# cc1200layout.net
KiCad netlist of a schematic drawn in EAGLE
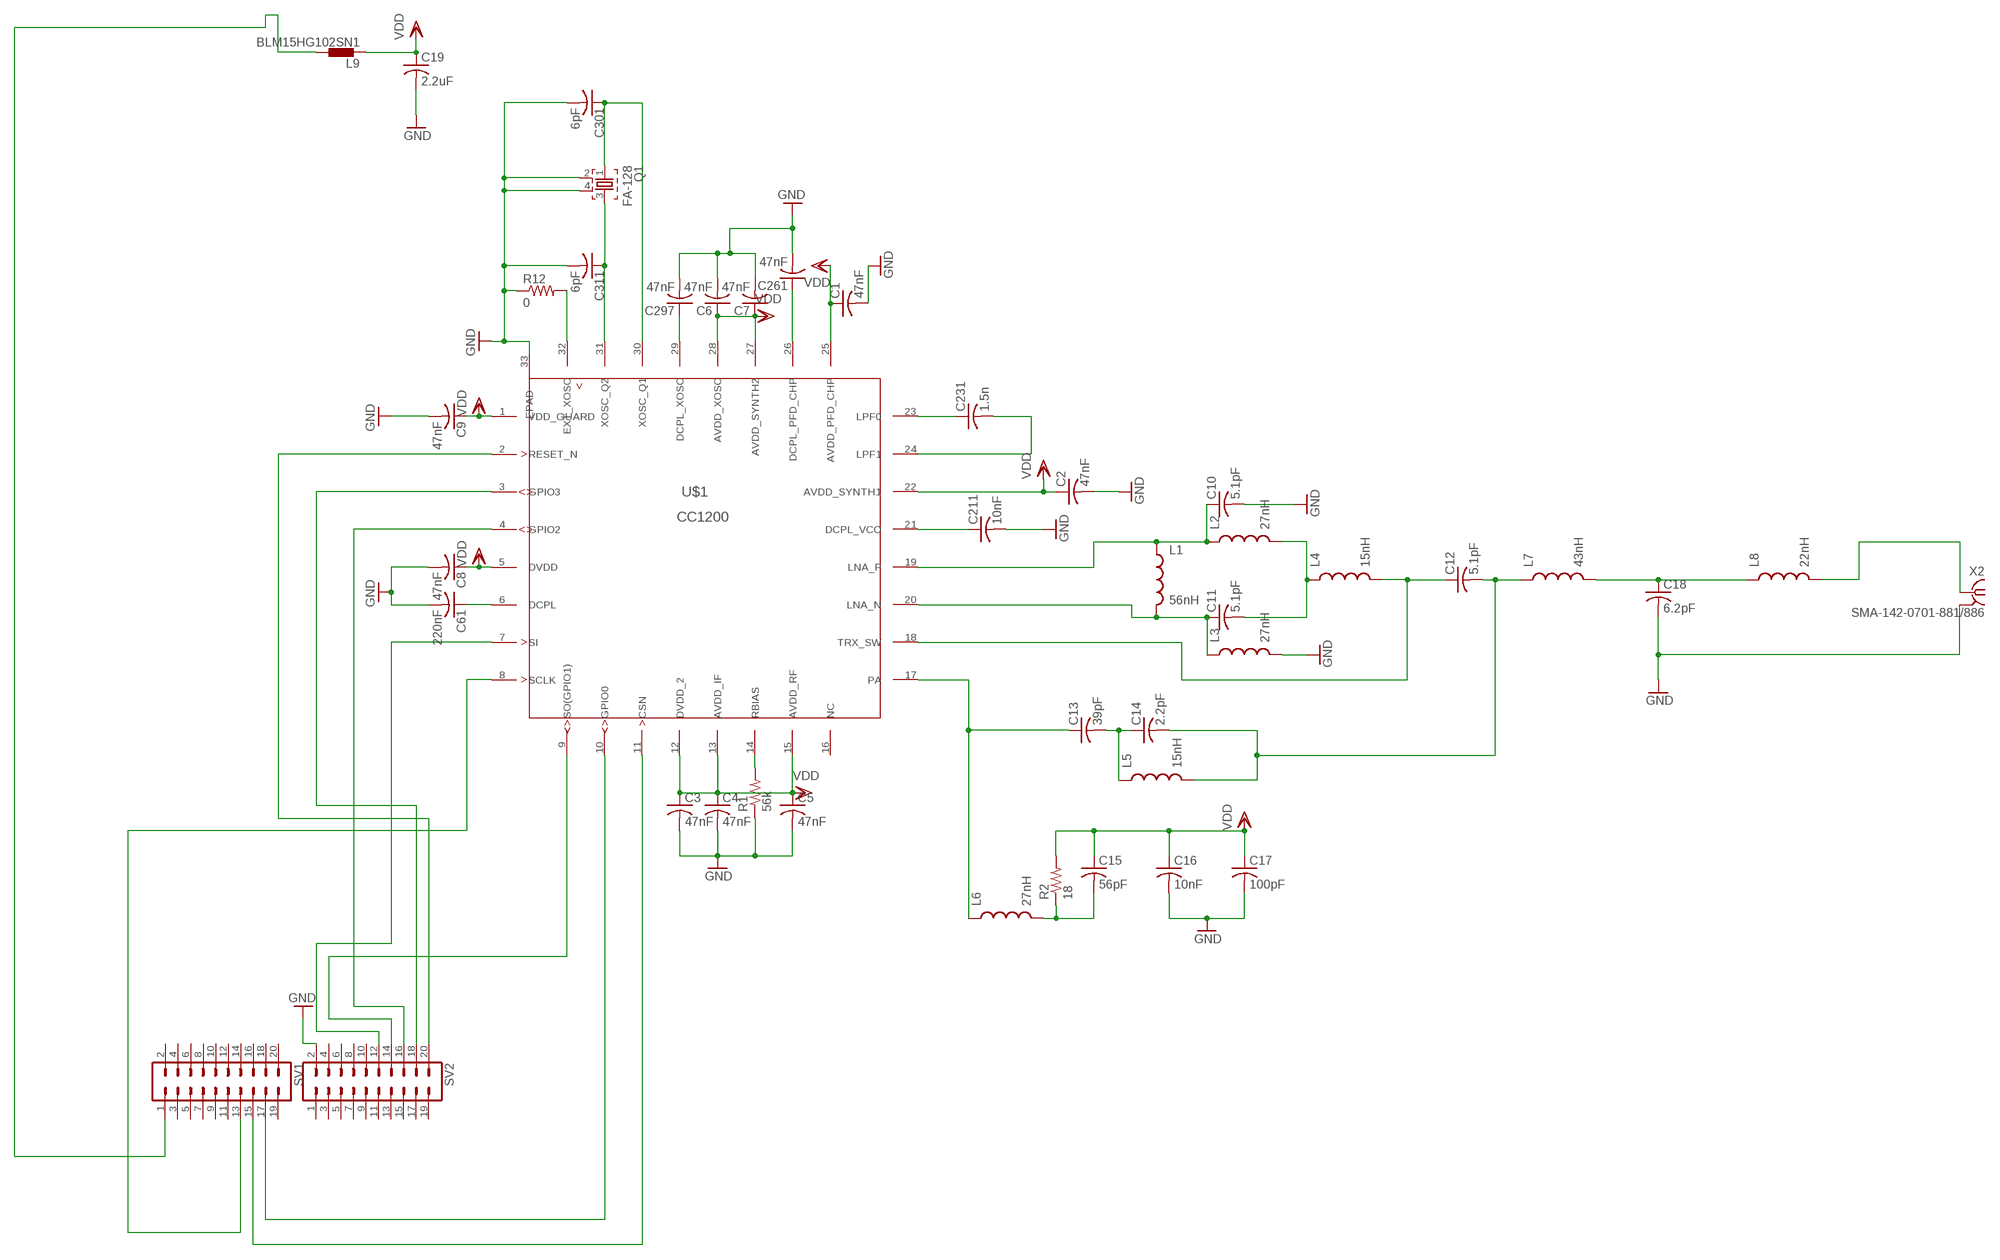
[diagram p0: schematic, sheet 1]

(export (version "E")
  (design (tool "Eeschema 10.0.6"))
  (components
    (comp (ref "C1")
      (value "47nF")
      (footprint "eagle-import:C0402K")
      (libsource (lib "eagle-import") (part "C-USC0402K"))
    )
    (comp (ref "C2")
      (value "47nF")
      (footprint "eagle-import:C0402K")
      (libsource (lib "eagle-import") (part "C-USC0402K"))
    )
    (comp (ref "C3")
      (value "47nF")
      (footprint "eagle-import:C0402K")
      (libsource (lib "eagle-import") (part "C-USC0402K"))
    )
    (comp (ref "C4")
      (value "47nF")
      (footprint "eagle-import:C0402K")
      (libsource (lib "eagle-import") (part "C-USC0402K"))
    )
    (comp (ref "C5")
      (value "47nF")
      (footprint "eagle-import:C0402K")
      (libsource (lib "eagle-import") (part "C-USC0402K"))
    )
    (comp (ref "C6")
      (value "47nF")
      (footprint "eagle-import:C0402K")
      (libsource (lib "eagle-import") (part "C-USC0402K"))
    )
    (comp (ref "C7")
      (value "47nF")
      (footprint "eagle-import:C0402K")
      (libsource (lib "eagle-import") (part "C-USC0402K"))
    )
    (comp (ref "C8")
      (value "47nF")
      (footprint "eagle-import:C0402K")
      (libsource (lib "eagle-import") (part "C-USC0402K"))
    )
    (comp (ref "C9")
      (value "47nF")
      (footprint "eagle-import:C0402K")
      (libsource (lib "eagle-import") (part "C-USC0402K"))
    )
    (comp (ref "C10")
      (value "5.1pF")
      (footprint "eagle-import:C0402K")
      (libsource (lib "eagle-import") (part "C-USC0402K"))
    )
    (comp (ref "C11")
      (value "5.1pF")
      (footprint "eagle-import:C0402K")
      (libsource (lib "eagle-import") (part "C-USC0402K"))
    )
    (comp (ref "C12")
      (value "5.1pF")
      (footprint "eagle-import:C0402K")
      (libsource (lib "eagle-import") (part "C-USC0402K"))
    )
    (comp (ref "C13")
      (value "39pF")
      (footprint "eagle-import:C0402K")
      (libsource (lib "eagle-import") (part "C-USC0402K"))
    )
    (comp (ref "C14")
      (value "2.2pF")
      (footprint "eagle-import:C0402K")
      (libsource (lib "eagle-import") (part "C-USC0402K"))
    )
    (comp (ref "C15")
      (value "56pF")
      (footprint "eagle-import:C0402K")
      (libsource (lib "eagle-import") (part "C-USC0402K"))
    )
    (comp (ref "C16")
      (value "10nF")
      (footprint "eagle-import:C0402K")
      (libsource (lib "eagle-import") (part "C-USC0402K"))
    )
    (comp (ref "C17")
      (value "100pF")
      (footprint "eagle-import:C0402K")
      (libsource (lib "eagle-import") (part "C-USC0402K"))
    )
    (comp (ref "C18")
      (value "6.2pF")
      (footprint "eagle-import:C0402K")
      (libsource (lib "eagle-import") (part "C-USC0402K"))
    )
    (comp (ref "C19")
      (value "2.2uF")
      (footprint "eagle-import:C0603K")
      (libsource (lib "eagle-import") (part "C-USC0603K"))
    )
    (comp (ref "C61")
      (value "220nF")
      (footprint "eagle-import:C0402K")
      (libsource (lib "eagle-import") (part "C-USC0402K"))
    )
    (comp (ref "C211")
      (value "10nF")
      (footprint "eagle-import:C0402K")
      (libsource (lib "eagle-import") (part "C-USC0402K"))
    )
    (comp (ref "C231")
      (value "1.5n")
      (footprint "eagle-import:C0402K")
      (libsource (lib "eagle-import") (part "C-USC0402K"))
    )
    (comp (ref "C261")
      (value "47nF")
      (footprint "eagle-import:C0402K")
      (libsource (lib "eagle-import") (part "C-USC0402K"))
    )
    (comp (ref "C297")
      (value "47nF")
      (footprint "eagle-import:C0402K")
      (libsource (lib "eagle-import") (part "C-USC0402K"))
    )
    (comp (ref "C301")
      (value "6pF")
      (footprint "eagle-import:C0402K")
      (libsource (lib "eagle-import") (part "C-USC0402K"))
    )
    (comp (ref "C311")
      (value "6pF")
      (footprint "eagle-import:C0402K")
      (libsource (lib "eagle-import") (part "C-USC0402K"))
    )
    (comp (ref "L1")
      (value "56nH")
      (footprint "eagle-import:C0402")
      (libsource (lib "eagle-import") (part "INDUCTOR0402"))
    )
    (comp (ref "L2")
      (value "27nH")
      (footprint "eagle-import:C0402")
      (libsource (lib "eagle-import") (part "INDUCTOR0402"))
    )
    (comp (ref "L3")
      (value "27nH")
      (footprint "eagle-import:C0402")
      (libsource (lib "eagle-import") (part "INDUCTOR0402"))
    )
    (comp (ref "L4")
      (value "15nH")
      (footprint "eagle-import:C0402")
      (libsource (lib "eagle-import") (part "INDUCTOR0402"))
    )
    (comp (ref "L5")
      (value "15nH")
      (footprint "eagle-import:C0402")
      (libsource (lib "eagle-import") (part "INDUCTOR0402"))
    )
    (comp (ref "L6")
      (value "27nH")
      (footprint "eagle-import:C0402")
      (libsource (lib "eagle-import") (part "INDUCTOR0402"))
    )
    (comp (ref "L7")
      (value "43nH")
      (footprint "eagle-import:C0402")
      (libsource (lib "eagle-import") (part "INDUCTOR0402"))
    )
    (comp (ref "L8")
      (value "22nH")
      (footprint "eagle-import:C0402")
      (libsource (lib "eagle-import") (part "INDUCTOR0402"))
    )
    (comp (ref "L9")
      (value "BLM15HG102SN1")
      (footprint "eagle-import:0402")
      (libsource (lib "eagle-import") (part "BLM15HG102SN1"))
    )
    (comp (ref "Q1")
      (value "FA-128")
      (footprint "eagle-import:FA-128")
      (libsource (lib "eagle-import") (part "FA-128"))
    )
    (comp (ref "R1")
      (value "56k")
      (footprint "eagle-import:R0402")
      (libsource (lib "eagle-import") (part "R-US_R0402"))
    )
    (comp (ref "R2")
      (value "18")
      (footprint "eagle-import:R0402")
      (libsource (lib "eagle-import") (part "R-US_R0402"))
    )
    (comp (ref "R12")
      (value "0")
      (footprint "eagle-import:R0402")
      (libsource (lib "eagle-import") (part "R-US_R0402"))
    )
    (comp (ref "SV1")
      (value "MA10-2")
      (footprint "eagle-import:MA10-2")
      (libsource (lib "eagle-import") (part "MA10-2"))
    )
    (comp (ref "SV2")
      (value "MA10-2")
      (footprint "eagle-import:MA10-2")
      (libsource (lib "eagle-import") (part "MA10-2"))
    )
    (comp (ref "U$1")
      (value "CC1200")
      (footprint "eagle-import:RHB32_3P45X3P45")
      (libsource (lib "eagle-import") (part "CC1200"))
    )
    (comp (ref "X2")
      (value "SMA-142-0701-881/886")
      (footprint "eagle-import:J502-ND-142-0701-881_886")
      (fields (field (name "MF") "JOHNSON COMPONENTS") (field (name "MPN") "142-0701-881"))
      (libsource (lib "eagle-import") (part "SMA-142-0701-881/886"))
    )
  )
  (nets
    (net (code "1") (name "GND") (class "Default")
      (node (ref "C1") (pin "2") (pinfunction "2_2") (pintype "passive"))
      (node (ref "C10") (pin "2") (pinfunction "2_2") (pintype "passive"))
      (node (ref "C16") (pin "2") (pinfunction "2_2") (pintype "passive"))
      (node (ref "C17") (pin "2") (pinfunction "2_2") (pintype "passive"))
      (node (ref "C18") (pin "2") (pinfunction "2_2") (pintype "passive"))
      (node (ref "C19") (pin "2") (pinfunction "2_2") (pintype "passive"))
      (node (ref "C2") (pin "2") (pinfunction "2_2") (pintype "passive"))
      (node (ref "C211") (pin "2") (pinfunction "2_2") (pintype "passive"))
      (node (ref "C261") (pin "2") (pinfunction "2_2") (pintype "passive"))
      (node (ref "C297") (pin "2") (pinfunction "2_2") (pintype "passive"))
      (node (ref "C3") (pin "2") (pinfunction "2_2") (pintype "passive"))
      (node (ref "C301") (pin "2") (pinfunction "2_2") (pintype "passive"))
      (node (ref "C311") (pin "2") (pinfunction "2_2") (pintype "passive"))
      (node (ref "C4") (pin "2") (pinfunction "2_2") (pintype "passive"))
      (node (ref "C5") (pin "2") (pinfunction "2_2") (pintype "passive"))
      (node (ref "C6") (pin "2") (pinfunction "2_2") (pintype "passive"))
      (node (ref "C61") (pin "2") (pinfunction "2_2") (pintype "passive"))
      (node (ref "C7") (pin "2") (pinfunction "2_2") (pintype "passive"))
      (node (ref "C8") (pin "2") (pinfunction "2_2") (pintype "passive"))
      (node (ref "C9") (pin "2") (pinfunction "2_2") (pintype "passive"))
      (node (ref "L3") (pin "2") (pinfunction "2_2") (pintype "passive"))
      (node (ref "Q1") (pin "2") (pinfunction "2_2") (pintype "passive"))
      (node (ref "Q1") (pin "4") (pinfunction "4_4") (pintype "passive"))
      (node (ref "R1") (pin "1") (pinfunction "1_1") (pintype "passive"))
      (node (ref "R12") (pin "1") (pinfunction "1_1") (pintype "passive"))
      (node (ref "SV2") (pin "2") (pinfunction "2_2") (pintype "passive"))
      (node (ref "U$1") (pin "33") (pinfunction "EPAD_33") (pintype "passive"))
      (node (ref "X2") (pin "G@1") (pinfunction "2_G@1") (pintype "passive"))
      (node (ref "X2") (pin "G@2") (pinfunction "2_G@2") (pintype "passive"))
      (node (ref "X2") (pin "G@3") (pinfunction "2_G@3") (pintype "passive"))
      (node (ref "X2") (pin "G@4") (pinfunction "2_G@4") (pintype "passive"))
    )
    (net (code "2") (name "Net-(C11-Pad2)") (class "Default")
      (node (ref "C11") (pin "2") (pinfunction "2_2") (pintype "passive"))
      (node (ref "L2") (pin "2") (pinfunction "2_2") (pintype "passive"))
      (node (ref "L4") (pin "1") (pinfunction "1_1") (pintype "passive"))
    )
    (net (code "3") (name "Net-(C12-Pad2)") (class "Default")
      (node (ref "C12") (pin "2") (pinfunction "2_2") (pintype "passive"))
      (node (ref "C14") (pin "2") (pinfunction "2_2") (pintype "passive"))
      (node (ref "L5") (pin "2") (pinfunction "2_2") (pintype "passive"))
      (node (ref "L7") (pin "1") (pinfunction "1_1") (pintype "passive"))
    )
    (net (code "4") (name "Net-(C13-Pad2)") (class "Default")
      (node (ref "C13") (pin "2") (pinfunction "2_2") (pintype "passive"))
      (node (ref "C14") (pin "1") (pinfunction "1_1") (pintype "passive"))
      (node (ref "L5") (pin "1") (pinfunction "1_1") (pintype "passive"))
    )
    (net (code "5") (name "Net-(C15-Pad2)") (class "Default")
      (node (ref "C15") (pin "2") (pinfunction "2_2") (pintype "passive"))
      (node (ref "L6") (pin "2") (pinfunction "2_2") (pintype "passive"))
      (node (ref "R2") (pin "1") (pinfunction "1_1") (pintype "passive"))
    )
    (net (code "6") (name "Net-(C18-Pad1)") (class "Default")
      (node (ref "C18") (pin "1") (pinfunction "1_1") (pintype "passive"))
      (node (ref "L7") (pin "2") (pinfunction "2_2") (pintype "passive"))
      (node (ref "L8") (pin "1") (pinfunction "1_1") (pintype "passive"))
    )
    (net (code "7") (name "Net-(L8-Pad2)") (class "Default")
      (node (ref "L8") (pin "2") (pinfunction "2_2") (pintype "passive"))
      (node (ref "X2") (pin "1") (pinfunction "1_1") (pintype "passive"))
    )
    (net (code "8") (name "Net-(L9-Pad2)") (class "Default")
      (node (ref "L9") (pin "2") (pinfunction "2_2") (pintype "passive"))
      (node (ref "SV1") (pin "1") (pinfunction "1_1") (pintype "passive"))
    )
    (net (code "9") (name "Net-(U$1-CSN)") (class "Default")
      (node (ref "SV1") (pin "15") (pinfunction "15_15") (pintype "passive"))
      (node (ref "U$1") (pin "11") (pinfunction "CSN_11") (pintype "passive"))
    )
    (net (code "10") (name "Net-(U$1-DCPL)") (class "Default")
      (node (ref "C61") (pin "1") (pinfunction "1_1") (pintype "passive"))
      (node (ref "U$1") (pin "6") (pinfunction "DCPL_6") (pintype "passive"))
    )
    (net (code "11") (name "Net-(U$1-DCPL_PFD_CHP)") (class "Default")
      (node (ref "C261") (pin "1") (pinfunction "1_1") (pintype "passive"))
      (node (ref "U$1") (pin "26") (pinfunction "DCPL_PFD_CHP_26") (pintype "passive"))
    )
    (net (code "12") (name "Net-(U$1-DCPL_VCO)") (class "Default")
      (node (ref "C211") (pin "1") (pinfunction "1_1") (pintype "passive"))
      (node (ref "U$1") (pin "21") (pinfunction "DCPL_VCO_21") (pintype "passive"))
    )
    (net (code "13") (name "Net-(U$1-DCPL_XOSC)") (class "Default")
      (node (ref "C297") (pin "1") (pinfunction "1_1") (pintype "passive"))
      (node (ref "U$1") (pin "29") (pinfunction "DCPL_XOSC_29") (pintype "passive"))
    )
    (net (code "14") (name "Net-(U$1-EXT_XOSC)") (class "Default")
      (node (ref "R12") (pin "2") (pinfunction "2_2") (pintype "passive"))
      (node (ref "U$1") (pin "32") (pinfunction "EXT_XOSC_32") (pintype "passive"))
    )
    (net (code "15") (name "Net-(U$1-GPIO0)") (class "Default")
      (node (ref "SV1") (pin "17") (pinfunction "17_17") (pintype "passive"))
      (node (ref "U$1") (pin "10") (pinfunction "GPIO0_10") (pintype "passive"))
    )
    (net (code "16") (name "Net-(U$1-GPIO2)") (class "Default")
      (node (ref "SV2") (pin "16") (pinfunction "16_16") (pintype "passive"))
      (node (ref "U$1") (pin "4") (pinfunction "GPIO2_4") (pintype "passive"))
    )
    (net (code "17") (name "Net-(U$1-GPIO3)") (class "Default")
      (node (ref "SV2") (pin "18") (pinfunction "18_18") (pintype "passive"))
      (node (ref "U$1") (pin "3") (pinfunction "GPIO3_3") (pintype "passive"))
    )
    (net (code "18") (name "Net-(U$1-LNA_N)") (class "Default")
      (node (ref "C11") (pin "1") (pinfunction "1_1") (pintype "passive"))
      (node (ref "L1") (pin "2") (pinfunction "2_2") (pintype "passive"))
      (node (ref "L3") (pin "1") (pinfunction "1_1") (pintype "passive"))
      (node (ref "U$1") (pin "20") (pinfunction "LNA_N_20") (pintype "passive"))
    )
    (net (code "19") (name "Net-(U$1-LNA_P)") (class "Default")
      (node (ref "C10") (pin "1") (pinfunction "1_1") (pintype "passive"))
      (node (ref "L1") (pin "1") (pinfunction "1_1") (pintype "passive"))
      (node (ref "L2") (pin "1") (pinfunction "1_1") (pintype "passive"))
      (node (ref "U$1") (pin "19") (pinfunction "LNA_P_19") (pintype "passive"))
    )
    (net (code "20") (name "Net-(U$1-LPF0)") (class "Default")
      (node (ref "C231") (pin "1") (pinfunction "1_1") (pintype "passive"))
      (node (ref "U$1") (pin "23") (pinfunction "LPF0_23") (pintype "passive"))
    )
    (net (code "21") (name "Net-(U$1-LPF1)") (class "Default")
      (node (ref "C231") (pin "2") (pinfunction "2_2") (pintype "passive"))
      (node (ref "U$1") (pin "24") (pinfunction "LPF1_24") (pintype "passive"))
    )
    (net (code "22") (name "Net-(U$1-PA)") (class "Default")
      (node (ref "C13") (pin "1") (pinfunction "1_1") (pintype "passive"))
      (node (ref "L6") (pin "1") (pinfunction "1_1") (pintype "passive"))
      (node (ref "U$1") (pin "17") (pinfunction "PA_17") (pintype "passive"))
    )
    (net (code "23") (name "Net-(U$1-RBIAS)") (class "Default")
      (node (ref "R1") (pin "2") (pinfunction "2_2") (pintype "passive"))
      (node (ref "U$1") (pin "14") (pinfunction "RBIAS_14") (pintype "passive"))
    )
    (net (code "24") (name "Net-(U$1-RESET_N)") (class "Default")
      (node (ref "SV2") (pin "20") (pinfunction "20_20") (pintype "passive"))
      (node (ref "U$1") (pin "2") (pinfunction "RESET_N_2") (pintype "passive"))
    )
    (net (code "25") (name "Net-(U$1-SCLK)") (class "Default")
      (node (ref "SV1") (pin "13") (pinfunction "13_13") (pintype "passive"))
      (node (ref "U$1") (pin "8") (pinfunction "SCLK_8") (pintype "passive"))
    )
    (net (code "26") (name "Net-(U$1-SI)") (class "Default")
      (node (ref "SV2") (pin "12") (pinfunction "12_12") (pintype "passive"))
      (node (ref "U$1") (pin "7") (pinfunction "SI_7") (pintype "passive"))
    )
    (net (code "27") (name "Net-(U$1-SO(GPIO1))") (class "Default")
      (node (ref "SV2") (pin "14") (pinfunction "14_14") (pintype "passive"))
      (node (ref "U$1") (pin "9") (pinfunction "SO(GPIO1)_9") (pintype "passive"))
    )
    (net (code "28") (name "Net-(U$1-TRX_SW)") (class "Default")
      (node (ref "C12") (pin "1") (pinfunction "1_1") (pintype "passive"))
      (node (ref "L4") (pin "2") (pinfunction "2_2") (pintype "passive"))
      (node (ref "U$1") (pin "18") (pinfunction "TRX_SW_18") (pintype "passive"))
    )
    (net (code "29") (name "Net-(U$1-XOSC_Q1)") (class "Default")
      (node (ref "C301") (pin "1") (pinfunction "1_1") (pintype "passive"))
      (node (ref "Q1") (pin "1") (pinfunction "1_1") (pintype "passive"))
      (node (ref "U$1") (pin "30") (pinfunction "XOSC_Q1_30") (pintype "passive"))
    )
    (net (code "30") (name "Net-(U$1-XOSC_Q2)") (class "Default")
      (node (ref "C311") (pin "1") (pinfunction "1_1") (pintype "passive"))
      (node (ref "Q1") (pin "3") (pinfunction "3_3") (pintype "passive"))
      (node (ref "U$1") (pin "31") (pinfunction "XOSC_Q2_31") (pintype "passive"))
    )
    (net (code "31") (name "VDD") (class "Default")
      (node (ref "C1") (pin "1") (pinfunction "1_1") (pintype "passive"))
      (node (ref "C15") (pin "1") (pinfunction "1_1") (pintype "passive"))
      (node (ref "C16") (pin "1") (pinfunction "1_1") (pintype "passive"))
      (node (ref "C17") (pin "1") (pinfunction "1_1") (pintype "passive"))
      (node (ref "C19") (pin "1") (pinfunction "1_1") (pintype "passive"))
      (node (ref "C2") (pin "1") (pinfunction "1_1") (pintype "passive"))
      (node (ref "C3") (pin "1") (pinfunction "1_1") (pintype "passive"))
      (node (ref "C4") (pin "1") (pinfunction "1_1") (pintype "passive"))
      (node (ref "C5") (pin "1") (pinfunction "1_1") (pintype "passive"))
      (node (ref "C6") (pin "1") (pinfunction "1_1") (pintype "passive"))
      (node (ref "C7") (pin "1") (pinfunction "1_1") (pintype "passive"))
      (node (ref "C8") (pin "1") (pinfunction "1_1") (pintype "passive"))
      (node (ref "C9") (pin "1") (pinfunction "1_1") (pintype "passive"))
      (node (ref "L9") (pin "1") (pinfunction "1_1") (pintype "passive"))
      (node (ref "R2") (pin "2") (pinfunction "2_2") (pintype "passive"))
      (node (ref "U$1") (pin "1") (pinfunction "VDD_GUARD_1") (pintype "passive"))
      (node (ref "U$1") (pin "12") (pinfunction "DVDD_2_12") (pintype "passive"))
      (node (ref "U$1") (pin "13") (pinfunction "AVDD_IF_13") (pintype "passive"))
      (node (ref "U$1") (pin "15") (pinfunction "AVDD_RF_15") (pintype "passive"))
      (node (ref "U$1") (pin "22") (pinfunction "AVDD_SYNTH1_22") (pintype "passive"))
      (node (ref "U$1") (pin "25") (pinfunction "AVDD_PFD_CHP_25") (pintype "passive"))
      (node (ref "U$1") (pin "27") (pinfunction "AVDD_SYNTH2_27") (pintype "passive"))
      (node (ref "U$1") (pin "28") (pinfunction "AVDD_XOSC_28") (pintype "passive"))
      (node (ref "U$1") (pin "5") (pinfunction "DVDD_5") (pintype "passive"))
    )
    (net (code "32") (name "unconnected-(SV1-Pad2)") (class "Default")
      (node (ref "SV1") (pin "2") (pinfunction "2_2") (pintype "passive"))
    )
    (net (code "33") (name "unconnected-(SV1-Pad3)") (class "Default")
      (node (ref "SV1") (pin "3") (pinfunction "3_3") (pintype "passive"))
    )
    (net (code "34") (name "unconnected-(SV1-Pad4)") (class "Default")
      (node (ref "SV1") (pin "4") (pinfunction "4_4") (pintype "passive"))
    )
    (net (code "35") (name "unconnected-(SV1-Pad5)") (class "Default")
      (node (ref "SV1") (pin "5") (pinfunction "5_5") (pintype "passive"))
    )
    (net (code "36") (name "unconnected-(SV1-Pad6)") (class "Default")
      (node (ref "SV1") (pin "6") (pinfunction "6_6") (pintype "passive"))
    )
    (net (code "37") (name "unconnected-(SV1-Pad7)") (class "Default")
      (node (ref "SV1") (pin "7") (pinfunction "7_7") (pintype "passive"))
    )
    (net (code "38") (name "unconnected-(SV1-Pad8)") (class "Default")
      (node (ref "SV1") (pin "8") (pinfunction "8_8") (pintype "passive"))
    )
    (net (code "39") (name "unconnected-(SV1-Pad9)") (class "Default")
      (node (ref "SV1") (pin "9") (pinfunction "9_9") (pintype "passive"))
    )
    (net (code "40") (name "unconnected-(SV1-Pad10)") (class "Default")
      (node (ref "SV1") (pin "10") (pinfunction "10_10") (pintype "passive"))
    )
    (net (code "41") (name "unconnected-(SV1-Pad11)") (class "Default")
      (node (ref "SV1") (pin "11") (pinfunction "11_11") (pintype "passive"))
    )
    (net (code "42") (name "unconnected-(SV1-Pad12)") (class "Default")
      (node (ref "SV1") (pin "12") (pinfunction "12_12") (pintype "passive"))
    )
    (net (code "43") (name "unconnected-(SV1-Pad14)") (class "Default")
      (node (ref "SV1") (pin "14") (pinfunction "14_14") (pintype "passive"))
    )
    (net (code "44") (name "unconnected-(SV1-Pad16)") (class "Default")
      (node (ref "SV1") (pin "16") (pinfunction "16_16") (pintype "passive"))
    )
    (net (code "45") (name "unconnected-(SV1-Pad18)") (class "Default")
      (node (ref "SV1") (pin "18") (pinfunction "18_18") (pintype "passive"))
    )
    (net (code "46") (name "unconnected-(SV1-Pad19)") (class "Default")
      (node (ref "SV1") (pin "19") (pinfunction "19_19") (pintype "passive"))
    )
    (net (code "47") (name "unconnected-(SV1-Pad20)") (class "Default")
      (node (ref "SV1") (pin "20") (pinfunction "20_20") (pintype "passive"))
    )
    (net (code "48") (name "unconnected-(SV2-Pad1)") (class "Default")
      (node (ref "SV2") (pin "1") (pinfunction "1_1") (pintype "passive"))
    )
    (net (code "49") (name "unconnected-(SV2-Pad3)") (class "Default")
      (node (ref "SV2") (pin "3") (pinfunction "3_3") (pintype "passive"))
    )
    (net (code "50") (name "unconnected-(SV2-Pad4)") (class "Default")
      (node (ref "SV2") (pin "4") (pinfunction "4_4") (pintype "passive"))
    )
    (net (code "51") (name "unconnected-(SV2-Pad5)") (class "Default")
      (node (ref "SV2") (pin "5") (pinfunction "5_5") (pintype "passive"))
    )
    (net (code "52") (name "unconnected-(SV2-Pad6)") (class "Default")
      (node (ref "SV2") (pin "6") (pinfunction "6_6") (pintype "passive"))
    )
    (net (code "53") (name "unconnected-(SV2-Pad7)") (class "Default")
      (node (ref "SV2") (pin "7") (pinfunction "7_7") (pintype "passive"))
    )
    (net (code "54") (name "unconnected-(SV2-Pad8)") (class "Default")
      (node (ref "SV2") (pin "8") (pinfunction "8_8") (pintype "passive"))
    )
    (net (code "55") (name "unconnected-(SV2-Pad9)") (class "Default")
      (node (ref "SV2") (pin "9") (pinfunction "9_9") (pintype "passive"))
    )
    (net (code "56") (name "unconnected-(SV2-Pad10)") (class "Default")
      (node (ref "SV2") (pin "10") (pinfunction "10_10") (pintype "passive"))
    )
    (net (code "57") (name "unconnected-(SV2-Pad11)") (class "Default")
      (node (ref "SV2") (pin "11") (pinfunction "11_11") (pintype "passive"))
    )
    (net (code "58") (name "unconnected-(SV2-Pad13)") (class "Default")
      (node (ref "SV2") (pin "13") (pinfunction "13_13") (pintype "passive"))
    )
    (net (code "59") (name "unconnected-(SV2-Pad15)") (class "Default")
      (node (ref "SV2") (pin "15") (pinfunction "15_15") (pintype "passive"))
    )
    (net (code "60") (name "unconnected-(SV2-Pad17)") (class "Default")
      (node (ref "SV2") (pin "17") (pinfunction "17_17") (pintype "passive"))
    )
    (net (code "61") (name "unconnected-(SV2-Pad19)") (class "Default")
      (node (ref "SV2") (pin "19") (pinfunction "19_19") (pintype "passive"))
    )
    (net (code "62") (name "unconnected-(U$1-NC-Pad16)") (class "Default")
      (node (ref "U$1") (pin "16") (pinfunction "NC_16") (pintype "passive"))
    )
  )
)
